# usbasp2lagig.net
KiCad netlist of a schematic drawn in EAGLE
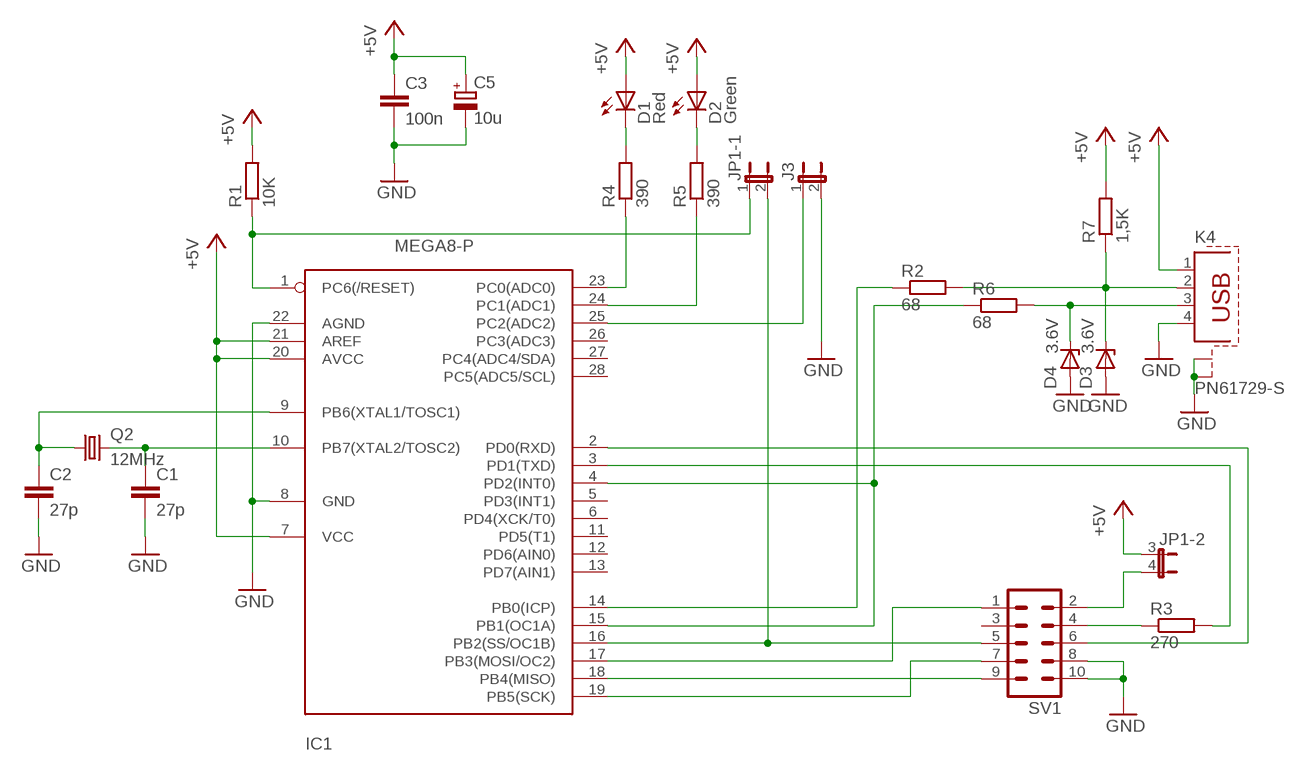
[diagram p0: schematic, sheet 1]

(export (version "E")
  (design (tool "Eeschema 10.0.6"))
  (components
    (comp (ref "C1")
      (value "27p")
      (footprint "eagle-import:C025-024X044")
      (libsource (lib "eagle-import") (part "C-EU025-024X044"))
    )
    (comp (ref "C2")
      (value "27p")
      (footprint "eagle-import:C025-024X044")
      (libsource (lib "eagle-import") (part "C-EU025-024X044"))
    )
    (comp (ref "C3")
      (value "100n")
      (footprint "eagle-import:C5B3")
      (libsource (lib "eagle-import") (part "C5/3"))
    )
    (comp (ref "C5")
      (value "10u")
      (footprint "eagle-import:E2,5-5")
      (libsource (lib "eagle-import") (part "CPOL-EUE2.5-5"))
    )
    (comp (ref "D1")
      (value "Red")
      (footprint "eagle-import:LED5MM")
      (libsource (lib "eagle-import") (part "LED5MM"))
    )
    (comp (ref "D2")
      (value "Green")
      (footprint "eagle-import:LED5MM")
      (libsource (lib "eagle-import") (part "LED5MM"))
    )
    (comp (ref "D3")
      (value "3.6V")
      (footprint "eagle-import:DO34Z7")
      (libsource (lib "eagle-import") (part "ZENER-DIODEDO34-7"))
    )
    (comp (ref "D4")
      (value "3.6V")
      (footprint "eagle-import:DO34Z7")
      (libsource (lib "eagle-import") (part "ZENER-DIODEDO34-7"))
    )
    (comp (ref "IC1")
      (value "MEGA8-P")
      (footprint "eagle-import:DIL28-3")
      (libsource (lib "eagle-import") (part "MEGA8-P"))
    )
    (comp (ref "J3")
      (value "JP1E")
      (footprint "eagle-import:JP1")
      (libsource (lib "eagle-import") (part "JP1E"))
    )
    (comp (ref "JP1")
      (value "JP2QE")
      (footprint "eagle-import:JP2Q")
      (libsource (lib "eagle-import") (part "JP2QE"))
    )
    (comp (ref "K4")
      (value "PN61729-S")
      (footprint "eagle-import:PN61729-S")
      (libsource (lib "eagle-import") (part "PN61729-S"))
    )
    (comp (ref "Q2")
      (value "12MHz")
      (footprint "eagle-import:HC49_S")
      (libsource (lib "eagle-import") (part "CRYSTALHC49S"))
    )
    (comp (ref "R1")
      (value "10K")
      (footprint "eagle-import:0207_7")
      (libsource (lib "eagle-import") (part "R-EU_0207/7"))
    )
    (comp (ref "R2")
      (value "68")
      (footprint "eagle-import:0207_7")
      (libsource (lib "eagle-import") (part "R-EU_0207/7"))
    )
    (comp (ref "R3")
      (value "270")
      (footprint "eagle-import:0207_7")
      (libsource (lib "eagle-import") (part "R-EU_0207/7"))
    )
    (comp (ref "R4")
      (value "390")
      (footprint "eagle-import:0207_7")
      (libsource (lib "eagle-import") (part "R-EU_0207/7"))
    )
    (comp (ref "R5")
      (value "390")
      (footprint "eagle-import:0207_7")
      (libsource (lib "eagle-import") (part "R-EU_0207/7"))
    )
    (comp (ref "R6")
      (value "68")
      (footprint "eagle-import:0207_7")
      (libsource (lib "eagle-import") (part "R-EU_0207/7"))
    )
    (comp (ref "R7")
      (value "1,5K")
      (footprint "eagle-import:0207_7")
      (libsource (lib "eagle-import") (part "R-EU_0207/7"))
    )
    (comp (ref "SV1")
      (value "ML10LANG")
      (footprint "eagle-import:ML10_LANG")
      (libsource (lib "eagle-import") (part "ML10LANG"))
    )
  )
  (nets
    (net (code "1") (name "+5V") (class "Default")
      (node (ref "C3") (pin "1") (pinfunction "1_1") (pintype "passive"))
      (node (ref "C5") (pin "+") (pinfunction "+_+") (pintype "passive"))
      (node (ref "D1") (pin "A") (pinfunction "A_A") (pintype "passive"))
      (node (ref "D2") (pin "A") (pinfunction "A_A") (pintype "passive"))
      (node (ref "IC1") (pin "20") (pinfunction "AVCC_20") (pintype "bidirectional"))
      (node (ref "IC1") (pin "21") (pinfunction "AREF_21") (pintype "bidirectional"))
      (node (ref "IC1") (pin "7") (pinfunction "VCC_7") (pintype "bidirectional"))
      (node (ref "JP1") (pin "3") (pinfunction "1_3") (pintype "passive"))
      (node (ref "K4") (pin "1") (pinfunction "1_1") (pintype "passive"))
      (node (ref "R1") (pin "2") (pinfunction "2_2") (pintype "passive"))
      (node (ref "R7") (pin "2") (pinfunction "2_2") (pintype "passive"))
    )
    (net (code "2") (name "GND") (class "Default")
      (node (ref "C1") (pin "2") (pinfunction "2_2") (pintype "passive"))
      (node (ref "C2") (pin "2") (pinfunction "2_2") (pintype "passive"))
      (node (ref "C3") (pin "2") (pinfunction "2_2") (pintype "passive"))
      (node (ref "C5") (pin "-") (pinfunction "-_-") (pintype "passive"))
      (node (ref "D3") (pin "A") (pinfunction "A_A") (pintype "passive"))
      (node (ref "D4") (pin "A") (pinfunction "A_A") (pintype "passive"))
      (node (ref "IC1") (pin "22") (pinfunction "AGND_22") (pintype "bidirectional"))
      (node (ref "IC1") (pin "8") (pinfunction "GND_8") (pintype "bidirectional"))
      (node (ref "J3") (pin "2") (pinfunction "2_2") (pintype "passive"))
      (node (ref "K4") (pin "4") (pinfunction "4_4") (pintype "passive"))
      (node (ref "K4") (pin "S1") (pinfunction "S1_S1") (pintype "passive"))
      (node (ref "K4") (pin "S2") (pinfunction "S2_S2") (pintype "passive"))
      (node (ref "SV1") (pin "10") (pinfunction "10_10") (pintype "passive"))
      (node (ref "SV1") (pin "8") (pinfunction "8_8") (pintype "passive"))
    )
    (net (code "3") (name "Net-(D1-C)") (class "Default")
      (node (ref "D1") (pin "K") (pinfunction "C_K") (pintype "passive"))
      (node (ref "R4") (pin "2") (pinfunction "2_2") (pintype "passive"))
    )
    (net (code "4") (name "Net-(D2-C)") (class "Default")
      (node (ref "D2") (pin "K") (pinfunction "C_K") (pintype "passive"))
      (node (ref "R5") (pin "2") (pinfunction "2_2") (pintype "passive"))
    )
    (net (code "5") (name "Net-(D3-PadC)") (class "Default")
      (node (ref "D3") (pin "C") (pinfunction "C_C") (pintype "passive"))
      (node (ref "K4") (pin "2") (pinfunction "2_2") (pintype "passive"))
      (node (ref "R2") (pin "2") (pinfunction "2_2") (pintype "passive"))
      (node (ref "R7") (pin "1") (pinfunction "1_1") (pintype "passive"))
    )
    (net (code "6") (name "Net-(D4-PadC)") (class "Default")
      (node (ref "D4") (pin "C") (pinfunction "C_C") (pintype "passive"))
      (node (ref "K4") (pin "3") (pinfunction "3_3") (pintype "passive"))
      (node (ref "R6") (pin "2") (pinfunction "2_2") (pintype "passive"))
    )
    (net (code "7") (name "Net-(IC1-PB0(ICP))") (class "Default")
      (node (ref "IC1") (pin "14") (pinfunction "PB0(ICP)_14") (pintype "bidirectional"))
      (node (ref "R2") (pin "1") (pinfunction "1_1") (pintype "passive"))
    )
    (net (code "8") (name "Net-(IC1-PB1(OC1A))") (class "Default")
      (node (ref "IC1") (pin "15") (pinfunction "PB1(OC1A)_15") (pintype "bidirectional"))
      (node (ref "IC1") (pin "4") (pinfunction "PD2(INT0)_4") (pintype "bidirectional"))
      (node (ref "R6") (pin "1") (pinfunction "1_1") (pintype "passive"))
    )
    (net (code "9") (name "Net-(IC1-PB2(SS{slash}OC1B))") (class "Default")
      (node (ref "IC1") (pin "16") (pinfunction "PB2(SS/OC1B)_16") (pintype "bidirectional"))
      (node (ref "JP1") (pin "2") (pinfunction "2_2") (pintype "passive"))
      (node (ref "SV1") (pin "5") (pinfunction "5_5") (pintype "passive"))
    )
    (net (code "10") (name "Net-(IC1-PB3(MOSI{slash}OC2))") (class "Default")
      (node (ref "IC1") (pin "17") (pinfunction "PB3(MOSI/OC2)_17") (pintype "bidirectional"))
      (node (ref "SV1") (pin "1") (pinfunction "1_1") (pintype "passive"))
    )
    (net (code "11") (name "Net-(IC1-PB4(MISO))") (class "Default")
      (node (ref "IC1") (pin "18") (pinfunction "PB4(MISO)_18") (pintype "bidirectional"))
      (node (ref "SV1") (pin "9") (pinfunction "9_9") (pintype "passive"))
    )
    (net (code "12") (name "Net-(IC1-PB5(SCK))") (class "Default")
      (node (ref "IC1") (pin "19") (pinfunction "PB5(SCK)_19") (pintype "bidirectional"))
      (node (ref "SV1") (pin "7") (pinfunction "7_7") (pintype "passive"))
    )
    (net (code "13") (name "Net-(IC1-PB6(XTAL1{slash}TOSC1))") (class "Default")
      (node (ref "C2") (pin "1") (pinfunction "1_1") (pintype "passive"))
      (node (ref "IC1") (pin "9") (pinfunction "PB6(XTAL1/TOSC1)_9") (pintype "bidirectional"))
      (node (ref "Q2") (pin "1") (pinfunction "1_1") (pintype "passive"))
    )
    (net (code "14") (name "Net-(IC1-PB7(XTAL2{slash}TOSC2))") (class "Default")
      (node (ref "C1") (pin "1") (pinfunction "1_1") (pintype "passive"))
      (node (ref "IC1") (pin "10") (pinfunction "PB7(XTAL2/TOSC2)_10") (pintype "bidirectional"))
      (node (ref "Q2") (pin "2") (pinfunction "2_2") (pintype "passive"))
    )
    (net (code "15") (name "Net-(IC1-PC0(ADC0))") (class "Default")
      (node (ref "IC1") (pin "23") (pinfunction "PC0(ADC0)_23") (pintype "bidirectional"))
      (node (ref "R4") (pin "1") (pinfunction "1_1") (pintype "passive"))
    )
    (net (code "16") (name "Net-(IC1-PC1(ADC1))") (class "Default")
      (node (ref "IC1") (pin "24") (pinfunction "PC1(ADC1)_24") (pintype "bidirectional"))
      (node (ref "R5") (pin "1") (pinfunction "1_1") (pintype "passive"))
    )
    (net (code "17") (name "Net-(IC1-PC2(ADC2))") (class "Default")
      (node (ref "IC1") (pin "25") (pinfunction "PC2(ADC2)_25") (pintype "bidirectional"))
      (node (ref "J3") (pin "1") (pinfunction "1_1") (pintype "passive"))
    )
    (net (code "18") (name "Net-(IC1-PC6({slash}RESET))") (class "Default")
      (node (ref "IC1") (pin "1") (pinfunction "PC6(/RESET)_1") (pintype "bidirectional"))
      (node (ref "JP1") (pin "1") (pinfunction "1_1") (pintype "passive"))
      (node (ref "R1") (pin "1") (pinfunction "1_1") (pintype "passive"))
    )
    (net (code "19") (name "Net-(IC1-PD0(RXD))") (class "Default")
      (node (ref "IC1") (pin "2") (pinfunction "PD0(RXD)_2") (pintype "bidirectional"))
      (node (ref "SV1") (pin "6") (pinfunction "6_6") (pintype "passive"))
    )
    (net (code "20") (name "Net-(IC1-PD1(TXD))") (class "Default")
      (node (ref "IC1") (pin "3") (pinfunction "PD1(TXD)_3") (pintype "bidirectional"))
      (node (ref "R3") (pin "2") (pinfunction "2_2") (pintype "passive"))
    )
    (net (code "21") (name "Net-(JP1B-2)") (class "Default")
      (node (ref "JP1") (pin "4") (pinfunction "2_4") (pintype "passive"))
      (node (ref "SV1") (pin "2") (pinfunction "2_2") (pintype "passive"))
    )
    (net (code "22") (name "Net-(R3-Pad1)") (class "Default")
      (node (ref "R3") (pin "1") (pinfunction "1_1") (pintype "passive"))
      (node (ref "SV1") (pin "4") (pinfunction "4_4") (pintype "passive"))
    )
    (net (code "23") (name "unconnected-(IC1-PC3(ADC3)-Pad26)") (class "Default")
      (node (ref "IC1") (pin "26") (pinfunction "PC3(ADC3)_26") (pintype "bidirectional"))
    )
    (net (code "24") (name "unconnected-(IC1-PC4(ADC4{slash}SDA)-Pad27)") (class "Default")
      (node (ref "IC1") (pin "27") (pinfunction "PC4(ADC4/SDA)_27") (pintype "bidirectional"))
    )
    (net (code "25") (name "unconnected-(IC1-PC5(ADC5{slash}SCL)-Pad28)") (class "Default")
      (node (ref "IC1") (pin "28") (pinfunction "PC5(ADC5/SCL)_28") (pintype "bidirectional"))
    )
    (net (code "26") (name "unconnected-(IC1-PD3(INT1)-Pad5)") (class "Default")
      (node (ref "IC1") (pin "5") (pinfunction "PD3(INT1)_5") (pintype "bidirectional"))
    )
    (net (code "27") (name "unconnected-(IC1-PD4(XCK{slash}T0)-Pad6)") (class "Default")
      (node (ref "IC1") (pin "6") (pinfunction "PD4(XCK/T0)_6") (pintype "bidirectional"))
    )
    (net (code "28") (name "unconnected-(IC1-PD5(T1)-Pad11)") (class "Default")
      (node (ref "IC1") (pin "11") (pinfunction "PD5(T1)_11") (pintype "bidirectional"))
    )
    (net (code "29") (name "unconnected-(IC1-PD6(AIN0)-Pad12)") (class "Default")
      (node (ref "IC1") (pin "12") (pinfunction "PD6(AIN0)_12") (pintype "bidirectional"))
    )
    (net (code "30") (name "unconnected-(IC1-PD7(AIN1)-Pad13)") (class "Default")
      (node (ref "IC1") (pin "13") (pinfunction "PD7(AIN1)_13") (pintype "bidirectional"))
    )
    (net (code "31") (name "unconnected-(SV1-Pad3)") (class "Default")
      (node (ref "SV1") (pin "3") (pinfunction "3_3") (pintype "passive"))
    )
  )
)
